# NSE2024_MORIMORI.net
KiCad netlist of a schematic drawn in EAGLE
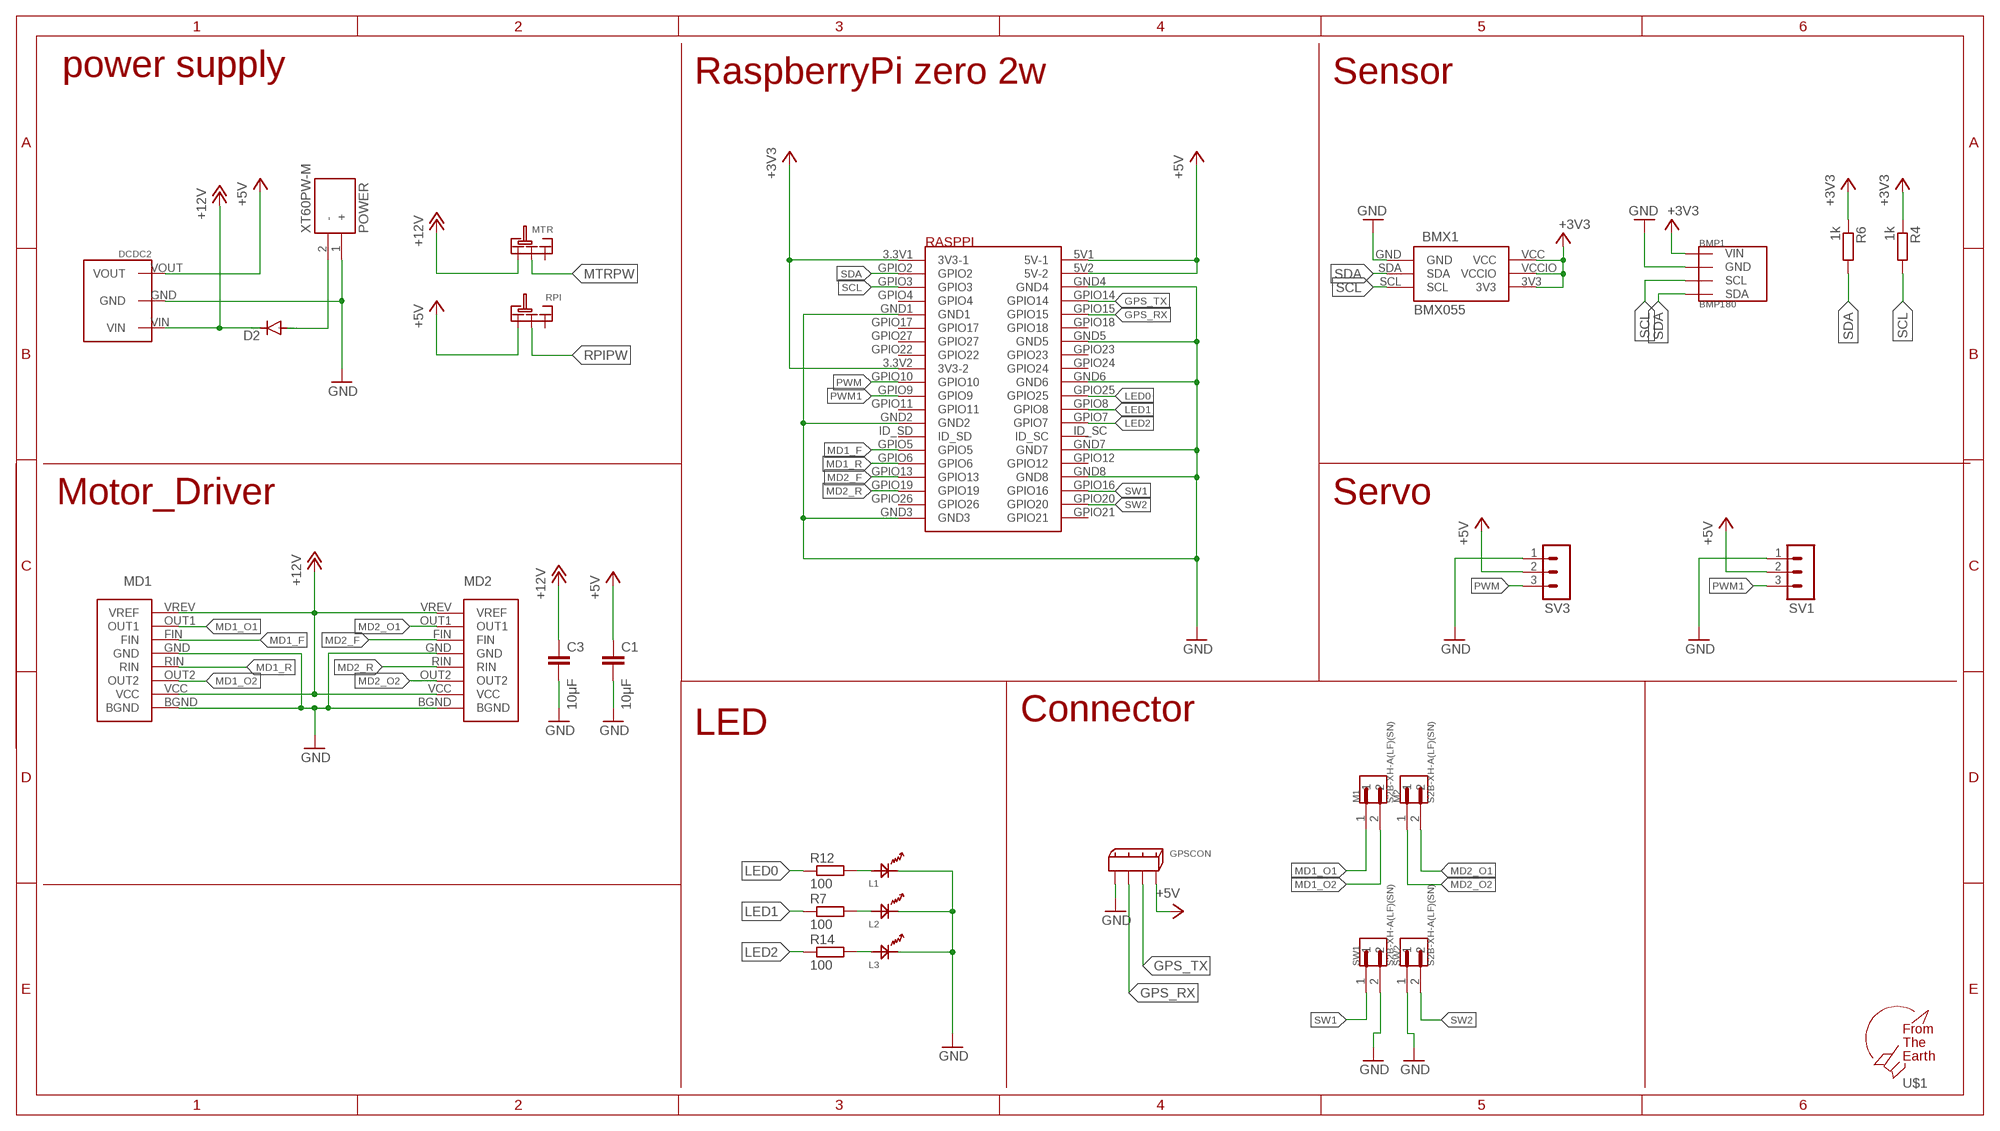
[diagram p0: schematic, sheet 1]

(export (version "E")
  (design (tool "Eeschema 10.0.6"))
  (components
    (comp (ref "BMP1")
      (value "BMP180")
      (footprint "eagle-import:GY-68")
      (libsource (lib "eagle-import") (part "BMP180"))
    )
    (comp (ref "BMX1")
      (value "BMX055")
      (footprint "eagle-import:BMX055")
      (libsource (lib "eagle-import") (part "BMX055"))
    )
    (comp (ref "C1")
      (value "10μF")
      (footprint "eagle-import:C0603")
      (libsource (lib "eagle-import") (part "C-EUC0603"))
    )
    (comp (ref "C3")
      (value "10μF")
      (footprint "eagle-import:C0603")
      (libsource (lib "eagle-import") (part "C-EUC0603"))
    )
    (comp (ref "D2")
      (value "1N4148DO35-7")
      (footprint "eagle-import:DO35-7")
      (libsource (lib "eagle-import") (part "1N4148DO35-7"))
    )
    (comp (ref "DCDC2")
      (value "3.3V1A_M78AR033-1")
      (footprint "eagle-import:3.3V1A_M78AR033-1")
      (libsource (lib "eagle-import") (part "3.3V1A_M78AR033-1"))
    )
    (comp (ref "GPSCON")
      (value "2.5_MINI-SPOX_4PIN")
      (footprint "eagle-import:2.5_MINI-SPOX_4PIN")
      (libsource (lib "eagle-import") (part "2.5_MINI-SPOX_4PIN"))
    )
    (comp (ref "L1")
      (value "OSXX1608C1A")
      (footprint "eagle-import:OSXX1608C1A")
      (libsource (lib "eagle-import") (part "OSXX1608C1A"))
    )
    (comp (ref "L2")
      (value "OSXX1608C1A")
      (footprint "eagle-import:OSXX1608C1A")
      (libsource (lib "eagle-import") (part "OSXX1608C1A"))
    )
    (comp (ref "L3")
      (value "OSXX1608C1A")
      (footprint "eagle-import:OSXX1608C1A")
      (libsource (lib "eagle-import") (part "OSXX1608C1A"))
    )
    (comp (ref "M1")
      (value "S2B-XH-A(LF)(SN)")
      (footprint "eagle-import:JST_S2B-XH-A(LF)(SN)")
      (fields (field (name "MF") "JST Sales America Inc."))
      (libsource (lib "eagle-import") (part "S2B-XH-A(LF)(SN)"))
    )
    (comp (ref "M2")
      (value "S2B-XH-A(LF)(SN)")
      (footprint "eagle-import:JST_S2B-XH-A(LF)(SN)")
      (fields (field (name "MF") "JST Sales America Inc."))
      (libsource (lib "eagle-import") (part "S2B-XH-A(LF)(SN)"))
    )
    (comp (ref "MD1")
      (value "BD6222HFP-TR")
      (footprint "eagle-import:BD6222HFP-TR")
      (libsource (lib "eagle-import") (part "BD6222HFP-TR"))
    )
    (comp (ref "MD2")
      (value "BD6222HFP-TR")
      (footprint "eagle-import:BD6222HFP-TR")
      (libsource (lib "eagle-import") (part "BD6222HFP-TR"))
    )
    (comp (ref "MTR")
      (value "SRIDE_SWITCH")
      (footprint "eagle-import:SRIDE_SWITCH")
      (libsource (lib "eagle-import") (part "SRIDE_SWITCH"))
    )
    (comp (ref "POWER")
      (value "XT60PW-M")
      (footprint "eagle-import:AMASS_XT60PW-M")
      (fields (field (name "MF") "AMASS"))
      (libsource (lib "eagle-import") (part "XT60PW-M"))
    )
    (comp (ref "R4")
      (value "1k")
      (footprint "eagle-import:R0603")
      (libsource (lib "eagle-import") (part "R-EU_R0603"))
    )
    (comp (ref "R6")
      (value "1k")
      (footprint "eagle-import:R0603")
      (libsource (lib "eagle-import") (part "R-EU_R0603"))
    )
    (comp (ref "R7")
      (value "100")
      (footprint "eagle-import:R0603")
      (libsource (lib "eagle-import") (part "R-EU_R0603"))
    )
    (comp (ref "R12")
      (value "100")
      (footprint "eagle-import:R0603")
      (libsource (lib "eagle-import") (part "R-EU_R0603"))
    )
    (comp (ref "R14")
      (value "100")
      (footprint "eagle-import:R0603")
      (libsource (lib "eagle-import") (part "R-EU_R0603"))
    )
    (comp (ref "RASPPI")
      (value "RASPBERYPIZEROW")
      (footprint "eagle-import:RASPBERYPIZEROW")
      (libsource (lib "eagle-import") (part "RASPBERYPIZEROW"))
    )
    (comp (ref "RPI")
      (value "SRIDE_SWITCH")
      (footprint "eagle-import:SRIDE_SWITCH")
      (libsource (lib "eagle-import") (part "SRIDE_SWITCH"))
    )
    (comp (ref "SV1")
      (value "MA03-1")
      (footprint "eagle-import:MA03-1")
      (libsource (lib "eagle-import") (part "MA03-1"))
    )
    (comp (ref "SV3")
      (value "MA03-1")
      (footprint "eagle-import:MA03-1")
      (libsource (lib "eagle-import") (part "MA03-1"))
    )
    (comp (ref "SW1")
      (value "S2B-XH-A(LF)(SN)")
      (footprint "eagle-import:JST_S2B-XH-A(LF)(SN)")
      (fields (field (name "MF") "JST Sales America Inc."))
      (libsource (lib "eagle-import") (part "S2B-XH-A(LF)(SN)"))
    )
    (comp (ref "SW2")
      (value "S2B-XH-A(LF)(SN)")
      (footprint "eagle-import:JST_S2B-XH-A(LF)(SN)")
      (fields (field (name "MF") "JST Sales America Inc."))
      (libsource (lib "eagle-import") (part "S2B-XH-A(LF)(SN)"))
    )
    (comp (ref "U$1")
      (value "F.T.E.LOGO")
      (footprint "eagle-import:LOGO")
      (libsource (lib "eagle-import") (part "F.T.E.LOGO"))
    )
  )
  (nets
    (net (code "1") (name "+3V3") (class "Default")
      (node (ref "BMP1") (pin "P1") (pinfunction "VIN_P1") (pintype "bidirectional"))
      (node (ref "BMX1") (pin "3V3") (pinfunction "3V3_3V3") (pintype "power_in"))
      (node (ref "BMX1") (pin "VCC") (pinfunction "VCC_VCC") (pintype "power_in"))
      (node (ref "BMX1") (pin "VCCIO") (pinfunction "VCCIO_VCCIO") (pintype "power_in"))
      (node (ref "R4") (pin "1") (pinfunction "1_1") (pintype "passive"))
      (node (ref "R6") (pin "1") (pinfunction "1_1") (pintype "passive"))
      (node (ref "RASPPI") (pin "3.3V1") (pinfunction "3V3-1_3.3V1") (pintype "bidirectional"))
      (node (ref "RASPPI") (pin "3.3V2") (pinfunction "3V3-2_3.3V2") (pintype "bidirectional"))
    )
    (net (code "2") (name "+5V") (class "Default")
      (node (ref "C1") (pin "1") (pinfunction "1_1") (pintype "passive"))
      (node (ref "DCDC2") (pin "VOUT") (pinfunction "VOUT_VOUT") (pintype "bidirectional"))
      (node (ref "GPSCON") (pin "P$4") (pinfunction "4_P$4") (pintype "bidirectional"))
      (node (ref "RASPPI") (pin "5V1") (pinfunction "5V-1_5V1") (pintype "bidirectional"))
      (node (ref "RASPPI") (pin "5V2") (pinfunction "5V-2_5V2") (pintype "bidirectional"))
      (node (ref "RPI") (pin "L") (pinfunction "L_L") (pintype "bidirectional"))
      (node (ref "SV1") (pin "2") (pinfunction "2_2") (pintype "passive"))
      (node (ref "SV3") (pin "2") (pinfunction "2_2") (pintype "passive"))
    )
    (net (code "3") (name "+12V") (class "Default")
      (node (ref "C3") (pin "1") (pinfunction "1_1") (pintype "passive"))
      (node (ref "D2") (pin "C") (pinfunction "C_C") (pintype "passive"))
      (node (ref "DCDC2") (pin "VIN") (pinfunction "VIN_VIN") (pintype "bidirectional"))
      (node (ref "MD1") (pin "VCC") (pinfunction "VCC_VCC") (pintype "bidirectional"))
      (node (ref "MD1") (pin "VREV") (pinfunction "VREF_VREV") (pintype "bidirectional"))
      (node (ref "MD2") (pin "VCC") (pinfunction "VCC_VCC") (pintype "bidirectional"))
      (node (ref "MD2") (pin "VREV") (pinfunction "VREF_VREV") (pintype "bidirectional"))
      (node (ref "MTR") (pin "L") (pinfunction "L_L") (pintype "bidirectional"))
    )
    (net (code "4") (name "GND") (class "Default")
      (node (ref "BMP1") (pin "P2") (pinfunction "GND_P2") (pintype "bidirectional"))
      (node (ref "BMX1") (pin "GND") (pinfunction "GND_GND") (pintype "power_in"))
      (node (ref "C1") (pin "2") (pinfunction "2_2") (pintype "passive"))
      (node (ref "C3") (pin "2") (pinfunction "2_2") (pintype "passive"))
      (node (ref "DCDC2") (pin "GND") (pinfunction "GND_GND") (pintype "bidirectional"))
      (node (ref "GPSCON") (pin "P$1") (pinfunction "1_P$1") (pintype "bidirectional"))
      (node (ref "L1") (pin "CT") (pinfunction "CT_CT") (pintype "bidirectional"))
      (node (ref "L2") (pin "CT") (pinfunction "CT_CT") (pintype "bidirectional"))
      (node (ref "L3") (pin "CT") (pinfunction "CT_CT") (pintype "bidirectional"))
      (node (ref "MD1") (pin "BGND") (pinfunction "BGND_BGND") (pintype "bidirectional"))
      (node (ref "MD1") (pin "GND") (pinfunction "GND_GND") (pintype "bidirectional"))
      (node (ref "MD2") (pin "BGND") (pinfunction "BGND_BGND") (pintype "bidirectional"))
      (node (ref "MD2") (pin "GND") (pinfunction "GND_GND") (pintype "bidirectional"))
      (node (ref "POWER") (pin "1") (pinfunction "+_1") (pintype "passive"))
      (node (ref "RASPPI") (pin "GND1") (pinfunction "GND1_GND1") (pintype "bidirectional"))
      (node (ref "RASPPI") (pin "GND2") (pinfunction "GND2_GND2") (pintype "bidirectional"))
      (node (ref "RASPPI") (pin "GND3") (pinfunction "GND3_GND3") (pintype "bidirectional"))
      (node (ref "RASPPI") (pin "GND4") (pinfunction "GND4_GND4") (pintype "bidirectional"))
      (node (ref "RASPPI") (pin "GND5") (pinfunction "GND5_GND5") (pintype "bidirectional"))
      (node (ref "RASPPI") (pin "GND6") (pinfunction "GND6_GND6") (pintype "bidirectional"))
      (node (ref "RASPPI") (pin "GND7") (pinfunction "GND7_GND7") (pintype "bidirectional"))
      (node (ref "RASPPI") (pin "GND8") (pinfunction "GND8_GND8") (pintype "bidirectional"))
      (node (ref "SV1") (pin "1") (pinfunction "1_1") (pintype "passive"))
      (node (ref "SV3") (pin "1") (pinfunction "1_1") (pintype "passive"))
      (node (ref "SW1") (pin "2") (pinfunction "2_2") (pintype "passive"))
      (node (ref "SW2") (pin "1") (pinfunction "1_1") (pintype "passive"))
    )
    (net (code "5") (name "GPS_RX") (class "Default")
      (node (ref "GPSCON") (pin "P$2") (pinfunction "2_P$2") (pintype "bidirectional"))
      (node (ref "RASPPI") (pin "GPIO15") (pinfunction "GPIO15_GPIO15") (pintype "bidirectional"))
    )
    (net (code "6") (name "GPS_TX") (class "Default")
      (node (ref "GPSCON") (pin "P$3") (pinfunction "3_P$3") (pintype "bidirectional"))
      (node (ref "RASPPI") (pin "GPIO14") (pinfunction "GPIO14_GPIO14") (pintype "bidirectional"))
    )
    (net (code "7") (name "LED0") (class "Default")
      (node (ref "R12") (pin "1") (pinfunction "1_1") (pintype "passive"))
      (node (ref "RASPPI") (pin "GPIO25") (pinfunction "GPIO25_GPIO25") (pintype "bidirectional"))
    )
    (net (code "8") (name "LED1") (class "Default")
      (node (ref "R7") (pin "1") (pinfunction "1_1") (pintype "passive"))
      (node (ref "RASPPI") (pin "GPIO8") (pinfunction "GPIO8_GPIO8") (pintype "bidirectional"))
    )
    (net (code "9") (name "LED2") (class "Default")
      (node (ref "R14") (pin "1") (pinfunction "1_1") (pintype "passive"))
      (node (ref "RASPPI") (pin "GPIO7") (pinfunction "GPIO7_GPIO7") (pintype "bidirectional"))
    )
    (net (code "10") (name "MD1_F") (class "Default")
      (node (ref "MD1") (pin "FIN") (pinfunction "FIN_FIN") (pintype "bidirectional"))
      (node (ref "RASPPI") (pin "GPIO5") (pinfunction "GPIO5_GPIO5") (pintype "bidirectional"))
    )
    (net (code "11") (name "MD1_O1") (class "Default")
      (node (ref "M1") (pin "1") (pinfunction "1_1") (pintype "passive"))
      (node (ref "MD1") (pin "OUT1") (pinfunction "OUT1_OUT1") (pintype "bidirectional"))
    )
    (net (code "12") (name "MD1_O2") (class "Default")
      (node (ref "M1") (pin "2") (pinfunction "2_2") (pintype "passive"))
      (node (ref "MD1") (pin "OUT2") (pinfunction "OUT2_OUT2") (pintype "bidirectional"))
    )
    (net (code "13") (name "MD1_R") (class "Default")
      (node (ref "MD1") (pin "RIN") (pinfunction "RIN_RIN") (pintype "bidirectional"))
      (node (ref "RASPPI") (pin "GPIO6") (pinfunction "GPIO6_GPIO6") (pintype "bidirectional"))
    )
    (net (code "14") (name "MD2_F") (class "Default")
      (node (ref "MD2") (pin "FIN") (pinfunction "FIN_FIN") (pintype "bidirectional"))
      (node (ref "RASPPI") (pin "GPIO13") (pinfunction "GPIO13_GPIO13") (pintype "bidirectional"))
    )
    (net (code "15") (name "MD2_O1") (class "Default")
      (node (ref "M2") (pin "2") (pinfunction "2_2") (pintype "passive"))
      (node (ref "MD2") (pin "OUT1") (pinfunction "OUT1_OUT1") (pintype "bidirectional"))
    )
    (net (code "16") (name "MD2_O2") (class "Default")
      (node (ref "M2") (pin "1") (pinfunction "1_1") (pintype "passive"))
      (node (ref "MD2") (pin "OUT2") (pinfunction "OUT2_OUT2") (pintype "bidirectional"))
    )
    (net (code "17") (name "MD2_R") (class "Default")
      (node (ref "MD2") (pin "RIN") (pinfunction "RIN_RIN") (pintype "bidirectional"))
      (node (ref "RASPPI") (pin "GPIO19") (pinfunction "GPIO19_GPIO19") (pintype "bidirectional"))
    )
    (net (code "18") (name "MTRPW") (class "Default")
      (node (ref "MTR") (pin "LR") (pinfunction "LR_LR") (pintype "bidirectional"))
    )
    (net (code "19") (name "Net-(L1-PadAN)") (class "Default")
      (node (ref "L1") (pin "AN") (pinfunction "AN_AN") (pintype "bidirectional"))
      (node (ref "R12") (pin "2") (pinfunction "2_2") (pintype "passive"))
    )
    (net (code "20") (name "Net-(L2-PadAN)") (class "Default")
      (node (ref "L2") (pin "AN") (pinfunction "AN_AN") (pintype "bidirectional"))
      (node (ref "R7") (pin "2") (pinfunction "2_2") (pintype "passive"))
    )
    (net (code "21") (name "Net-(L3-PadAN)") (class "Default")
      (node (ref "L3") (pin "AN") (pinfunction "AN_AN") (pintype "bidirectional"))
      (node (ref "R14") (pin "2") (pinfunction "2_2") (pintype "passive"))
    )
    (net (code "22") (name "Net-(POWER--)") (class "Default")
      (node (ref "D2") (pin "A") (pinfunction "A_A") (pintype "passive"))
      (node (ref "POWER") (pin "2") (pinfunction "-_2") (pintype "passive"))
    )
    (net (code "23") (name "PWM") (class "Default")
      (node (ref "RASPPI") (pin "GPIO10") (pinfunction "GPIO10_GPIO10") (pintype "bidirectional"))
      (node (ref "SV3") (pin "3") (pinfunction "3_3") (pintype "passive"))
    )
    (net (code "24") (name "PWM1") (class "Default")
      (node (ref "RASPPI") (pin "GPIO9") (pinfunction "GPIO9_GPIO9") (pintype "bidirectional"))
      (node (ref "SV1") (pin "3") (pinfunction "3_3") (pintype "passive"))
    )
    (net (code "25") (name "RPIPW") (class "Default")
      (node (ref "RPI") (pin "LR") (pinfunction "LR_LR") (pintype "bidirectional"))
    )
    (net (code "26") (name "SCL") (class "Default")
      (node (ref "BMP1") (pin "P3") (pinfunction "SCL_P3") (pintype "bidirectional"))
      (node (ref "BMX1") (pin "SCL") (pinfunction "SCL_SCL") (pintype "bidirectional"))
      (node (ref "R4") (pin "2") (pinfunction "2_2") (pintype "passive"))
      (node (ref "RASPPI") (pin "GPIO3") (pinfunction "GPIO3_GPIO3") (pintype "bidirectional"))
    )
    (net (code "27") (name "SDA") (class "Default")
      (node (ref "BMP1") (pin "P4") (pinfunction "SDA_P4") (pintype "bidirectional"))
      (node (ref "BMX1") (pin "SDA") (pinfunction "SDA_SDA") (pintype "bidirectional"))
      (node (ref "R6") (pin "2") (pinfunction "2_2") (pintype "passive"))
      (node (ref "RASPPI") (pin "GPIO2") (pinfunction "GPIO2_GPIO2") (pintype "bidirectional"))
    )
    (net (code "28") (name "SW1") (class "Default")
      (node (ref "RASPPI") (pin "GPIO16") (pinfunction "GPIO16_GPIO16") (pintype "bidirectional"))
      (node (ref "SW1") (pin "1") (pinfunction "1_1") (pintype "passive"))
    )
    (net (code "29") (name "SW2") (class "Default")
      (node (ref "RASPPI") (pin "GPIO20") (pinfunction "GPIO20_GPIO20") (pintype "bidirectional"))
      (node (ref "SW2") (pin "2") (pinfunction "2_2") (pintype "passive"))
    )
    (net (code "30") (name "unconnected-(MTR-PadR)") (class "Default")
      (node (ref "MTR") (pin "R") (pinfunction "R_R") (pintype "bidirectional"))
    )
    (net (code "31") (name "unconnected-(RASPPI-PadGPIO4)") (class "Default")
      (node (ref "RASPPI") (pin "GPIO4") (pinfunction "GPIO4_GPIO4") (pintype "bidirectional"))
    )
    (net (code "32") (name "unconnected-(RASPPI-PadGPIO11)") (class "Default")
      (node (ref "RASPPI") (pin "GPIO11") (pinfunction "GPIO11_GPIO11") (pintype "bidirectional"))
    )
    (net (code "33") (name "unconnected-(RASPPI-PadGPIO12)") (class "Default")
      (node (ref "RASPPI") (pin "GPIO12") (pinfunction "GPIO12_GPIO12") (pintype "bidirectional"))
    )
    (net (code "34") (name "unconnected-(RASPPI-PadGPIO17)") (class "Default")
      (node (ref "RASPPI") (pin "GPIO17") (pinfunction "GPIO17_GPIO17") (pintype "bidirectional"))
    )
    (net (code "35") (name "unconnected-(RASPPI-PadGPIO18)") (class "Default")
      (node (ref "RASPPI") (pin "GPIO18") (pinfunction "GPIO18_GPIO18") (pintype "bidirectional"))
    )
    (net (code "36") (name "unconnected-(RASPPI-PadGPIO21)") (class "Default")
      (node (ref "RASPPI") (pin "GPIO21") (pinfunction "GPIO21_GPIO21") (pintype "bidirectional"))
    )
    (net (code "37") (name "unconnected-(RASPPI-PadGPIO22)") (class "Default")
      (node (ref "RASPPI") (pin "GPIO22") (pinfunction "GPIO22_GPIO22") (pintype "bidirectional"))
    )
    (net (code "38") (name "unconnected-(RASPPI-PadGPIO23)") (class "Default")
      (node (ref "RASPPI") (pin "GPIO23") (pinfunction "GPIO23_GPIO23") (pintype "bidirectional"))
    )
    (net (code "39") (name "unconnected-(RASPPI-PadGPIO24)") (class "Default")
      (node (ref "RASPPI") (pin "GPIO24") (pinfunction "GPIO24_GPIO24") (pintype "bidirectional"))
    )
    (net (code "40") (name "unconnected-(RASPPI-PadGPIO26)") (class "Default")
      (node (ref "RASPPI") (pin "GPIO26") (pinfunction "GPIO26_GPIO26") (pintype "bidirectional"))
    )
    (net (code "41") (name "unconnected-(RASPPI-PadGPIO27)") (class "Default")
      (node (ref "RASPPI") (pin "GPIO27") (pinfunction "GPIO27_GPIO27") (pintype "bidirectional"))
    )
    (net (code "42") (name "unconnected-(RASPPI-PadID_SC)") (class "Default")
      (node (ref "RASPPI") (pin "ID_SC") (pinfunction "ID_SC_ID_SC") (pintype "bidirectional"))
    )
    (net (code "43") (name "unconnected-(RASPPI-PadID_SD)") (class "Default")
      (node (ref "RASPPI") (pin "ID_SD") (pinfunction "ID_SD_ID_SD") (pintype "bidirectional"))
    )
    (net (code "44") (name "unconnected-(RPI-PadR)") (class "Default")
      (node (ref "RPI") (pin "R") (pinfunction "R_R") (pintype "bidirectional"))
    )
  )
)
